# clock.net
KiCad netlist of a schematic drawn in Altium Designer
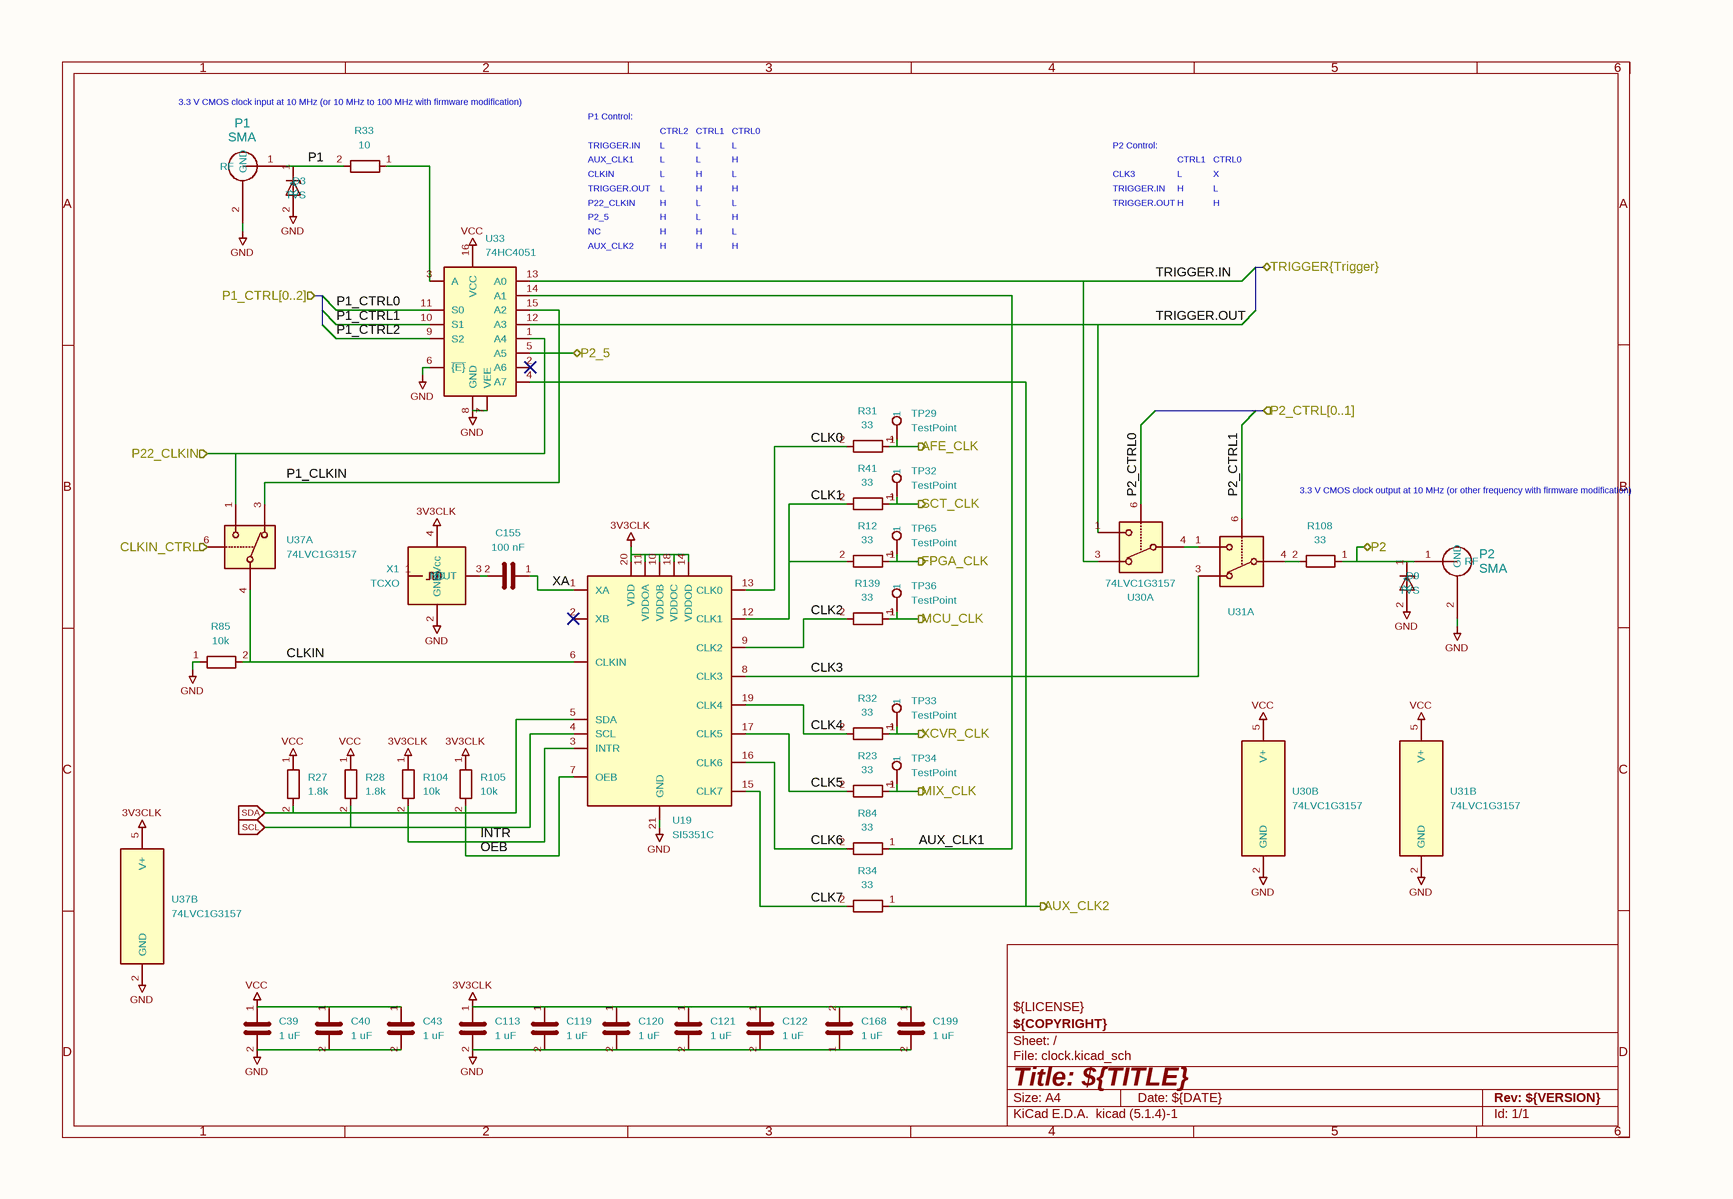
[diagram p0: clock.SchDoc]

(export (version "E")
  (design (tool "Eeschema 10.0.6"))
  (components
    (comp (ref "C39")
      (value "1 uF")
      (footprint "C_0402_1005Metric")
      (description "CAP CER 1UF 25V X5R 0402")
      (fields (field (name "MANUFACTURER") "Samsung") (field (name "PART NUMBER") "CL05A105KA5NQNC"))
      (libsource (lib "Device") (part "C"))
    )
    (comp (ref "C40")
      (value "1 uF")
      (footprint "C_0402_1005Metric")
      (description "CAP CER 1UF 25V X5R 0402")
      (fields (field (name "MANUFACTURER") "Samsung") (field (name "PART NUMBER") "CL05A105KA5NQNC"))
      (libsource (lib "Device") (part "C"))
    )
    (comp (ref "C43")
      (value "1 uF")
      (footprint "C_0402_1005Metric")
      (description "CAP CER 1UF 25V X5R 0402")
      (fields (field (name "MANUFACTURER") "Samsung") (field (name "PART NUMBER") "CL05A105KA5NQNC"))
      (libsource (lib "Device") (part "C"))
    )
    (comp (ref "C113")
      (value "1 uF")
      (footprint "C_0402_1005Metric")
      (description "CAP CER 1UF 25V X5R 0402")
      (fields (field (name "MANUFACTURER") "Samsung") (field (name "PART NUMBER") "CL05A105KA5NQNC"))
      (libsource (lib "Device") (part "C"))
    )
    (comp (ref "C119")
      (value "1 uF")
      (footprint "C_0402_1005Metric")
      (description "CAP CER 1UF 25V X5R 0402")
      (fields (field (name "MANUFACTURER") "Samsung") (field (name "PART NUMBER") "CL05A105KA5NQNC"))
      (libsource (lib "Device") (part "C"))
    )
    (comp (ref "C120")
      (value "1 uF")
      (footprint "C_0402_1005Metric")
      (description "CAP CER 1UF 25V X5R 0402")
      (fields (field (name "MANUFACTURER") "Samsung") (field (name "PART NUMBER") "CL05A105KA5NQNC"))
      (libsource (lib "Device") (part "C"))
    )
    (comp (ref "C121")
      (value "1 uF")
      (footprint "C_0402_1005Metric")
      (description "CAP CER 1UF 25V X5R 0402")
      (fields (field (name "MANUFACTURER") "Samsung") (field (name "PART NUMBER") "CL05A105KA5NQNC"))
      (libsource (lib "Device") (part "C"))
    )
    (comp (ref "C122")
      (value "1 uF")
      (footprint "C_0402_1005Metric")
      (description "CAP CER 1UF 25V X5R 0402")
      (fields (field (name "MANUFACTURER") "Samsung") (field (name "PART NUMBER") "CL05A105KA5NQNC"))
      (libsource (lib "Device") (part "C"))
    )
    (comp (ref "C155")
      (value "100 nF")
      (footprint "C_0402_1005Metric")
      (description "CAP CER 0.1UF 25V X5R 0402")
      (fields (field (name "MANUFACTURER") "Samsung") (field (name "PART NUMBER") "CL05A104KA5NNNC"))
      (libsource (lib "Device") (part "C"))
    )
    (comp (ref "C168")
      (value "1 uF")
      (footprint "C_0402_1005Metric")
      (description "CAP CER 1UF 25V X5R 0402")
      (fields (field (name "MANUFACTURER") "Samsung") (field (name "PART NUMBER") "CL05A105KA5NQNC"))
      (libsource (lib "Device") (part "C"))
    )
    (comp (ref "C199")
      (value "1 uF")
      (footprint "C_0402_1005Metric")
      (description "CAP CER 1UF 25V X5R 0402")
      (fields (field (name "MANUFACTURER") "Samsung") (field (name "PART NUMBER") "CL05A105KA5NQNC"))
      (libsource (lib "Device") (part "C"))
    )
    (comp (ref "D3")
      (value "TVS")
      (footprint "TSLP-2-19")
      (description "TVS DIODE 3.3V UNIDIRECTIONAL DFN1006")
      (fields (field (name "MANUFACTURER") "Slkor") (field (name "PART NUMBER") "SLESD0301L"))
      (libsource (lib "Device") (part "D_Zener"))
    )
    (comp (ref "D9")
      (value "TVS")
      (footprint "TSLP-2-19")
      (description "TVS DIODE 3.3V UNIDIRECTIONAL DFN1006")
      (fields (field (name "MANUFACTURER") "Slkor") (field (name "PART NUMBER") "SLESD0301L"))
      (libsource (lib "Device") (part "D_Zener"))
    )
    (comp (ref "P1")
      (value "SMA")
      (footprint "SMA_MyAntenna_A-SMA-KE-16.5A_EdgeMount")
      (description "CONN SMA RCPT STR 50OHM EDGE MNT")
      (fields (field (name "MANUFACTURER") "MyAntenna") (field (name "PART NUMBER") "A-SMA-KE-16.5A"))
      (libsource (lib "hackrf") (part "GSG-RF-CONN"))
    )
    (comp (ref "P2")
      (value "SMA")
      (footprint "SMA_MyAntenna_A-SMA-KE-16.5A_EdgeMount")
      (description "CONN SMA RCPT STR 50OHM EDGE MNT")
      (fields (field (name "MANUFACTURER") "MyAntenna") (field (name "PART NUMBER") "A-SMA-KE-16.5A"))
      (libsource (lib "hackrf") (part "GSG-RF-CONN"))
    )
    (comp (ref "R12")
      (value "33")
      (footprint "R_0201_0603Metric")
      (description "RES 33 OHM 5% 1/20W 0201")
      (fields (field (name "MANUFACTURER") "Yageo") (field (name "PART NUMBER") "RC0201JR-0733RL"))
      (libsource (lib "Device") (part "R"))
    )
    (comp (ref "R23")
      (value "33")
      (footprint "R_0201_0603Metric")
      (description "RES 33 OHM 5% 1/20W 0201")
      (fields (field (name "MANUFACTURER") "Yageo") (field (name "PART NUMBER") "RC0201JR-0733RL"))
      (libsource (lib "Device") (part "R"))
    )
    (comp (ref "R27")
      (value "1.8k")
      (footprint "R_0402_1005Metric")
      (description "RES 1.8K OHM 5% 1/16W 0402")
      (fields (field (name "MANUFACTURER") "Yageo") (field (name "PART NUMBER") "RC0402JR-071K8L"))
      (libsource (lib "") (part "R_1"))
    )
    (comp (ref "R28")
      (value "1.8k")
      (footprint "R_0402_1005Metric")
      (description "RES 1.8K OHM 5% 1/16W 0402")
      (fields (field (name "MANUFACTURER") "Yageo") (field (name "PART NUMBER") "RC0402JR-071K8L"))
      (libsource (lib "") (part "R_1"))
    )
    (comp (ref "R31")
      (value "33")
      (footprint "R_0201_0603Metric")
      (description "RES 33 OHM 5% 1/20W 0201")
      (fields (field (name "MANUFACTURER") "Yageo") (field (name "PART NUMBER") "RC0201JR-0733RL"))
      (libsource (lib "Device") (part "R"))
    )
    (comp (ref "R32")
      (value "33")
      (footprint "R_0201_0603Metric")
      (description "RES 33 OHM 5% 1/20W 0201")
      (fields (field (name "MANUFACTURER") "Yageo") (field (name "PART NUMBER") "RC0201JR-0733RL"))
      (libsource (lib "Device") (part "R"))
    )
    (comp (ref "R33")
      (value "10")
      (footprint "R_0201_0603Metric")
      (description "RES 10 OHM 5% 1/20W 0201")
      (fields (field (name "MANUFACTURER") "Yageo") (field (name "PART NUMBER") "RC0201JR-0710RL"))
      (libsource (lib "Device") (part "R"))
    )
    (comp (ref "R34")
      (value "33")
      (footprint "R_0201_0603Metric")
      (description "RES 33 OHM 5% 1/20W 0201")
      (fields (field (name "MANUFACTURER") "Yageo") (field (name "PART NUMBER") "RC0201JR-0733RL"))
      (libsource (lib "Device") (part "R"))
    )
    (comp (ref "R41")
      (value "33")
      (footprint "R_0201_0603Metric")
      (description "RES 33 OHM 5% 1/20W 0201")
      (fields (field (name "MANUFACTURER") "Yageo") (field (name "PART NUMBER") "RC0201JR-0733RL"))
      (libsource (lib "Device") (part "R"))
    )
    (comp (ref "R84")
      (value "33")
      (footprint "R_0201_0603Metric")
      (description "RES 33 OHM 5% 1/20W 0201")
      (fields (field (name "MANUFACTURER") "Yageo") (field (name "PART NUMBER") "RC0201JR-0733RL"))
      (libsource (lib "Device") (part "R"))
    )
    (comp (ref "R85")
      (value "10k")
      (footprint "R_0402_1005Metric")
      (description "RES 10K OHM 1/16W 5% 0402 SMD")
      (fields (field (name "MANUFACTURER") "Yageo") (field (name "PART NUMBER") "RC0402JR-0710KL"))
      (libsource (lib "") (part "R_2"))
    )
    (comp (ref "R104")
      (value "10k")
      (footprint "R_0402_1005Metric")
      (description "RES 10K OHM 1/16W 5% 0402 SMD")
      (fields (field (name "MANUFACTURER") "Yageo") (field (name "PART NUMBER") "RC0402JR-0710KL"))
      (libsource (lib "") (part "R_1"))
    )
    (comp (ref "R105")
      (value "10k")
      (footprint "R_0402_1005Metric")
      (description "RES 10K OHM 1/16W 5% 0402 SMD")
      (fields (field (name "MANUFACTURER") "Yageo") (field (name "PART NUMBER") "RC0402JR-0710KL"))
      (libsource (lib "") (part "R_1"))
    )
    (comp (ref "R108")
      (value "33")
      (footprint "R_0201_0603Metric")
      (description "RES 33 OHM 5% 1/20W 0201")
      (fields (field (name "MANUFACTURER") "Yageo") (field (name "PART NUMBER") "RC0201JR-0733RL"))
      (libsource (lib "Device") (part "R"))
    )
    (comp (ref "R139")
      (value "33")
      (footprint "R_0201_0603Metric")
      (description "RES 33 OHM 5% 1/20W 0201")
      (fields (field (name "MANUFACTURER") "Yageo") (field (name "PART NUMBER") "RC0201JR-0733RL"))
      (libsource (lib "Device") (part "R"))
    )
    (comp (ref "TP29")
      (value "TestPoint")
      (footprint "TestPoint_Pad_D1.0mm")
      (libsource (lib "Connector") (part "TestPoint"))
    )
    (comp (ref "TP32")
      (value "TestPoint")
      (footprint "TestPoint_Pad_D1.0mm")
      (libsource (lib "Connector") (part "TestPoint"))
    )
    (comp (ref "TP33")
      (value "TestPoint")
      (footprint "TestPoint_Pad_D1.0mm")
      (libsource (lib "Connector") (part "TestPoint"))
    )
    (comp (ref "TP34")
      (value "TestPoint")
      (footprint "TestPoint_Pad_D1.0mm")
      (libsource (lib "Connector") (part "TestPoint"))
    )
    (comp (ref "TP36")
      (value "TestPoint")
      (footprint "TestPoint_Pad_D1.0mm")
      (libsource (lib "Connector") (part "TestPoint"))
    )
    (comp (ref "TP65")
      (value "TestPoint")
      (footprint "TestPoint_Pad_D1.0mm")
      (libsource (lib "Connector") (part "TestPoint"))
    )
    (comp (ref "U19")
      (value "SI5351C")
      (footprint "QFN-20-1EP_4x4mm_P0.5mm_EP2.7x2.7mm_ThermalVias")
      (description "IC CLK GENERATOR 160MHZ 20QFN")
      (fields
        (field (name "MANUFACTURER") "Silicon Laboratories Inc")
        (field (name "PART NUMBER") "SI5351C-B-GM")
      )
      (libsource (lib "Oscillator") (part "Si5351C-B-GM"))
    )
    (comp (ref "U30")
      (value "74LVC1G3157")
      (footprint "SOT-363_SC-70-6")
      (description "IC SW SPDT-NO/NCX1 7OHM SC70-6")
      (fields (field (name "MANUFACTURER") "UMW") (field (name "PART NUMBER") "ET3157"))
      (libsource (lib "") (part "NC7SB3157P6X_1"))
    )
    (comp (ref "U31")
      (value "74LVC1G3157")
      (footprint "SOT-363_SC-70-6")
      (description "IC SW SPDT-NO/NCX1 7OHM SC70-6")
      (fields (field (name "MANUFACTURER") "UMW") (field (name "PART NUMBER") "ET3157"))
      (libsource (lib "") (part "NC7SB3157P6X_1"))
    )
    (comp (ref "U33")
      (value "74HC4051")
      (footprint "DHVQFN-16-1EP_2.5x3.5mm_P0.5mm_EP1x2mm")
      (description "IC MUX 8:1 120OHM 16DHVQFN")
      (fields (field (name "MANUFACTURER") "Nexperia") (field (name "PART NUMBER") "74HC4051BQ,115"))
      (libsource (lib "74xx") (part "74HC4051"))
    )
    (comp (ref "U37")
      (value "74LVC1G3157")
      (footprint "SOT-363_SC-70-6")
      (description "IC SW SPDT-NO/NCX1 7OHM SC70-6")
      (fields (field (name "MANUFACTURER") "UMW") (field (name "PART NUMBER") "ET3157"))
      (libsource (lib "Analog_Switch") (part "NC7SB3157P6X"))
    )
    (comp (ref "X1")
      (value "TCXO")
      (footprint "Oscillator_SMD_SeikoEpson_TG2520SMN-xxx-xxxxxx-4Pin_2.5x2.0mm")
      (description "25 MHz TCXO")
      (fields (field (name "MANUFACTURER") "HCI") (field (name "PART NUMBER") "8122S-25.000NQ33FTL"))
      (libsource (lib "Oscillator") (part "TG2520SMN-xx.xxxxxxMhz-xxxxNM"))
    )
  )
  (nets
    (net (code "2") (name "/AFE_CLK") (class "Default")
      (node (ref "R31") (pin "1") (pinfunction "1_1") (pintype "passive"))
      (node (ref "TP29") (pin "1") (pinfunction "1_1") (pintype "passive"))
    )
    (net (code "3") (name "/AUX_CLK1") (class "Default")
      (node (ref "R84") (pin "1") (pinfunction "1_1") (pintype "passive"))
      (node (ref "U33") (pin "14") (pinfunction "A1_14") (pintype "passive"))
    )
    (net (code "4") (name "/AUX_CLK2") (class "Default")
      (node (ref "R34") (pin "1") (pinfunction "1_1") (pintype "passive"))
      (node (ref "U33") (pin "4") (pinfunction "A7_4") (pintype "passive"))
    )
    (net (code "5") (name "/CLK0") (class "Default")
      (node (ref "R31") (pin "2") (pinfunction "2_2") (pintype "passive"))
      (node (ref "U19") (pin "13") (pinfunction "CLK0_13") (pintype "passive"))
    )
    (net (code "6") (name "/CLK1") (class "Default")
      (node (ref "R12") (pin "2") (pinfunction "2_2") (pintype "passive"))
      (node (ref "R41") (pin "2") (pinfunction "2_2") (pintype "passive"))
      (node (ref "U19") (pin "12") (pinfunction "CLK1_12") (pintype "passive"))
    )
    (net (code "7") (name "/CLK2") (class "Default")
      (node (ref "R139") (pin "2") (pinfunction "2_2") (pintype "passive"))
      (node (ref "U19") (pin "9") (pinfunction "CLK2_9") (pintype "passive"))
    )
    (net (code "8") (name "/CLK3") (class "Default")
      (node (ref "U19") (pin "8") (pinfunction "CLK3_8") (pintype "passive"))
      (node (ref "U31") (pin "3") (pinfunction "3_3") (pintype "passive"))
    )
    (net (code "9") (name "/CLK4") (class "Default")
      (node (ref "R32") (pin "2") (pinfunction "2_2") (pintype "passive"))
      (node (ref "U19") (pin "19") (pinfunction "CLK4_19") (pintype "passive"))
    )
    (net (code "10") (name "/CLK5") (class "Default")
      (node (ref "R23") (pin "2") (pinfunction "2_2") (pintype "passive"))
      (node (ref "U19") (pin "17") (pinfunction "CLK5_17") (pintype "passive"))
    )
    (net (code "11") (name "/CLK6") (class "Default")
      (node (ref "R84") (pin "2") (pinfunction "2_2") (pintype "passive"))
      (node (ref "U19") (pin "16") (pinfunction "CLK6_16") (pintype "passive"))
    )
    (net (code "12") (name "/CLK7") (class "Default")
      (node (ref "R34") (pin "2") (pinfunction "2_2") (pintype "passive"))
      (node (ref "U19") (pin "15") (pinfunction "CLK7_15") (pintype "passive"))
    )
    (net (code "13") (name "/CLKIN") (class "Default")
      (node (ref "R85") (pin "2") (pinfunction "2_2") (pintype "passive"))
      (node (ref "U19") (pin "6") (pinfunction "CLKIN_6") (pintype "passive"))
      (node (ref "U37") (pin "4") (pinfunction "4_4") (pintype "passive"))
    )
    (net (code "14") (name "/CLKIN_CTRL") (class "Default")
      (node (ref "U37") (pin "6") (pinfunction "6_6") (pintype "passive"))
    )
    (net (code "15") (name "/FPGA_CLK") (class "Default")
      (node (ref "R12") (pin "1") (pinfunction "1_1") (pintype "passive"))
      (node (ref "TP65") (pin "1") (pinfunction "1_1") (pintype "passive"))
    )
    (net (code "16") (name "/INTR") (class "Default")
      (node (ref "R104") (pin "2") (pinfunction "2_2") (pintype "passive"))
      (node (ref "U19") (pin "3") (pinfunction "INTR_3") (pintype "passive"))
    )
    (net (code "17") (name "/MCU_CLK") (class "Default")
      (node (ref "R139") (pin "1") (pinfunction "1_1") (pintype "passive"))
      (node (ref "TP36") (pin "1") (pinfunction "1_1") (pintype "passive"))
    )
    (net (code "18") (name "/MIX_CLK") (class "Default")
      (node (ref "R23") (pin "1") (pinfunction "1_1") (pintype "passive"))
      (node (ref "TP34") (pin "1") (pinfunction "1_1") (pintype "passive"))
    )
    (net (code "19") (name "/OEB") (class "Default")
      (node (ref "R105") (pin "2") (pinfunction "2_2") (pintype "passive"))
      (node (ref "U19") (pin "7") (pinfunction "OEB_7") (pintype "passive"))
    )
    (net (code "20") (name "/P1") (class "Default")
      (node (ref "D3") (pin "1") (pinfunction "K_1") (pintype "passive"))
      (node (ref "P1") (pin "1") (pinfunction "RF_1") (pintype "passive"))
      (node (ref "R33") (pin "2") (pinfunction "2_2") (pintype "passive"))
    )
    (net (code "21") (name "/P1_CLKIN") (class "Default")
      (node (ref "U33") (pin "15") (pinfunction "A2_15") (pintype "passive"))
      (node (ref "U37") (pin "3") (pinfunction "3_3") (pintype "passive"))
    )
    (net (code "22") (name "/P1_CTRL0") (class "Default")
      (node (ref "U33") (pin "11") (pinfunction "S0_11") (pintype "passive"))
    )
    (net (code "23") (name "/P1_CTRL1") (class "Default")
      (node (ref "U33") (pin "10") (pinfunction "S1_10") (pintype "passive"))
    )
    (net (code "24") (name "/P1_CTRL2") (class "Default")
      (node (ref "U33") (pin "9") (pinfunction "S2_9") (pintype "passive"))
    )
    (net (code "26") (name "/P2") (class "Default")
      (node (ref "D9") (pin "1") (pinfunction "K_1") (pintype "passive"))
      (node (ref "P2") (pin "1") (pinfunction "RF_1") (pintype "passive"))
      (node (ref "R108") (pin "1") (pinfunction "1_1") (pintype "passive"))
    )
    (net (code "27") (name "/P2_5") (class "Default")
      (node (ref "U33") (pin "5") (pinfunction "A5_5") (pintype "passive"))
    )
    (net (code "28") (name "/P2_CTRL0") (class "Default")
      (node (ref "U30") (pin "6") (pinfunction "6_6") (pintype "passive"))
    )
    (net (code "29") (name "/P2_CTRL1") (class "Default")
      (node (ref "U31") (pin "6") (pinfunction "6_6") (pintype "passive"))
    )
    (net (code "31") (name "/P22_CLKIN") (class "Default")
      (node (ref "U33") (pin "1") (pinfunction "A4_1") (pintype "passive"))
      (node (ref "U37") (pin "1") (pinfunction "1_1") (pintype "passive"))
    )
    (net (code "32") (name "/SCL") (class "Default")
      (node (ref "R28") (pin "2") (pinfunction "2_2") (pintype "passive"))
      (node (ref "U19") (pin "4") (pinfunction "SCL_4") (pintype "passive"))
    )
    (net (code "33") (name "/SCT_CLK") (class "Default")
      (node (ref "R41") (pin "1") (pinfunction "1_1") (pintype "passive"))
      (node (ref "TP32") (pin "1") (pinfunction "1_1") (pintype "passive"))
    )
    (net (code "34") (name "/SDA") (class "Default")
      (node (ref "R27") (pin "2") (pinfunction "2_2") (pintype "passive"))
      (node (ref "U19") (pin "5") (pinfunction "SDA_5") (pintype "passive"))
    )
    (net (code "35") (name "/TRIGGER.IN") (class "Default")
      (node (ref "U30") (pin "3") (pinfunction "3_3") (pintype "passive"))
      (node (ref "U33") (pin "13") (pinfunction "A0_13") (pintype "passive"))
    )
    (net (code "36") (name "/TRIGGER.OUT") (class "Default")
      (node (ref "U30") (pin "1") (pinfunction "1_1") (pintype "passive"))
      (node (ref "U33") (pin "12") (pinfunction "A3_12") (pintype "passive"))
    )
    (net (code "38") (name "/XA") (class "Default")
      (node (ref "C155") (pin "1") (pinfunction "1_1") (pintype "passive"))
      (node (ref "U19") (pin "1") (pinfunction "XA_1") (pintype "passive"))
    )
    (net (code "39") (name "/XCVR_CLK") (class "Default")
      (node (ref "R32") (pin "1") (pinfunction "1_1") (pintype "passive"))
      (node (ref "TP33") (pin "1") (pinfunction "1_1") (pintype "passive"))
    )
    (net (code "40") (name "3V3CLK") (class "Default")
      (node (ref "C113") (pin "1") (pinfunction "1_1") (pintype "passive"))
      (node (ref "C119") (pin "1") (pinfunction "1_1") (pintype "passive"))
      (node (ref "C120") (pin "1") (pinfunction "1_1") (pintype "passive"))
      (node (ref "C121") (pin "1") (pinfunction "1_1") (pintype "passive"))
      (node (ref "C122") (pin "1") (pinfunction "1_1") (pintype "passive"))
      (node (ref "C168") (pin "2") (pinfunction "2_2") (pintype "passive"))
      (node (ref "C199") (pin "1") (pinfunction "1_1") (pintype "passive"))
      (node (ref "R104") (pin "1") (pinfunction "1_1") (pintype "passive"))
      (node (ref "R105") (pin "1") (pinfunction "1_1") (pintype "passive"))
      (node (ref "U19") (pin "10") (pinfunction "VDDOB_10") (pintype "passive"))
      (node (ref "U19") (pin "11") (pinfunction "VDDOA_11") (pintype "passive"))
      (node (ref "U19") (pin "14") (pinfunction "VDDOD_14") (pintype "passive"))
      (node (ref "U19") (pin "18") (pinfunction "VDDOC_18") (pintype "passive"))
      (node (ref "U19") (pin "20") (pinfunction "VDD_20") (pintype "passive"))
      (node (ref "U37") (pin "5") (pinfunction "V+_5") (pintype "passive"))
      (node (ref "X1") (pin "4") (pinfunction "Vcc_4") (pintype "passive"))
    )
    (net (code "41") (name "GND") (class "Default")
      (node (ref "C113") (pin "2") (pinfunction "2_2") (pintype "passive"))
      (node (ref "C119") (pin "2") (pinfunction "2_2") (pintype "passive"))
      (node (ref "C120") (pin "2") (pinfunction "2_2") (pintype "passive"))
      (node (ref "C121") (pin "2") (pinfunction "2_2") (pintype "passive"))
      (node (ref "C122") (pin "2") (pinfunction "2_2") (pintype "passive"))
      (node (ref "C168") (pin "1") (pinfunction "1_1") (pintype "passive"))
      (node (ref "C199") (pin "2") (pinfunction "2_2") (pintype "passive"))
      (node (ref "C39") (pin "2") (pinfunction "2_2") (pintype "passive"))
      (node (ref "C40") (pin "2") (pinfunction "2_2") (pintype "passive"))
      (node (ref "C43") (pin "2") (pinfunction "2_2") (pintype "passive"))
      (node (ref "D3") (pin "2") (pinfunction "A_2") (pintype "passive"))
      (node (ref "D9") (pin "2") (pinfunction "A_2") (pintype "passive"))
      (node (ref "P1") (pin "2") (pinfunction "GND_2") (pintype "passive"))
      (node (ref "P2") (pin "2") (pinfunction "GND_2") (pintype "passive"))
      (node (ref "R85") (pin "1") (pinfunction "1_1") (pintype "passive"))
      (node (ref "U19") (pin "21") (pinfunction "GND_21") (pintype "passive"))
      (node (ref "U30") (pin "2") (pinfunction "GND_2") (pintype "passive"))
      (node (ref "U31") (pin "2") (pinfunction "GND_2") (pintype "passive"))
      (node (ref "U33") (pin "6") (pinfunction "~{{E}}_6") (pintype "passive"))
      (node (ref "U33") (pin "7") (pinfunction "VEE_7") (pintype "passive"))
      (node (ref "U33") (pin "8") (pinfunction "GND_8") (pintype "passive"))
      (node (ref "U37") (pin "2") (pinfunction "GND_2") (pintype "passive"))
      (node (ref "X1") (pin "2") (pinfunction "GND_2") (pintype "passive"))
    )
    (net (code "42") (name "Net-(R108-Pad2)") (class "Default")
      (node (ref "R108") (pin "2") (pinfunction "2_2") (pintype "passive"))
      (node (ref "U31") (pin "4") (pinfunction "4_4") (pintype "passive"))
    )
    (net (code "43") (name "Net-(U30-Pad4)") (class "Default")
      (node (ref "U30") (pin "4") (pinfunction "4_4") (pintype "passive"))
      (node (ref "U31") (pin "1") (pinfunction "1_1") (pintype "passive"))
    )
    (net (code "44") (name "Net-(U33-A)") (class "Default")
      (node (ref "R33") (pin "1") (pinfunction "1_1") (pintype "passive"))
      (node (ref "U33") (pin "3") (pinfunction "A_3") (pintype "passive"))
    )
    (net (code "45") (name "Net-(X1-OUT)") (class "Default")
      (node (ref "C155") (pin "2") (pinfunction "2_2") (pintype "passive"))
      (node (ref "X1") (pin "3") (pinfunction "OUT_3") (pintype "passive"))
    )
    (net (code "46") (name "VCC") (class "Default")
      (node (ref "C39") (pin "1") (pinfunction "1_1") (pintype "passive"))
      (node (ref "C40") (pin "1") (pinfunction "1_1") (pintype "passive"))
      (node (ref "C43") (pin "1") (pinfunction "1_1") (pintype "passive"))
      (node (ref "R27") (pin "1") (pinfunction "1_1") (pintype "passive"))
      (node (ref "R28") (pin "1") (pinfunction "1_1") (pintype "passive"))
      (node (ref "U30") (pin "5") (pinfunction "V+_5") (pintype "passive"))
      (node (ref "U31") (pin "5") (pinfunction "V+_5") (pintype "passive"))
      (node (ref "U33") (pin "16") (pinfunction "VCC_16") (pintype "passive"))
    )
    (net (code "47") (name "unconnected-(U19-XB-Pad2)") (class "Default")
      (node (ref "U19") (pin "2") (pinfunction "XB_2") (pintype "passive+no_connect"))
    )
    (net (code "48") (name "unconnected-(U33-A6-Pad2)") (class "Default")
      (node (ref "U33") (pin "2") (pinfunction "A6_2") (pintype "passive+no_connect"))
    )
    (net (code "49") (name "unconnected-(X1-NC-Pad1)") (class "Default")
      (node (ref "X1") (pin "1") (pinfunction "NC_1") (pintype "passive"))
    )
  )
)
